# simp1.net
KiCad netlist of a schematic drawn in EAGLE
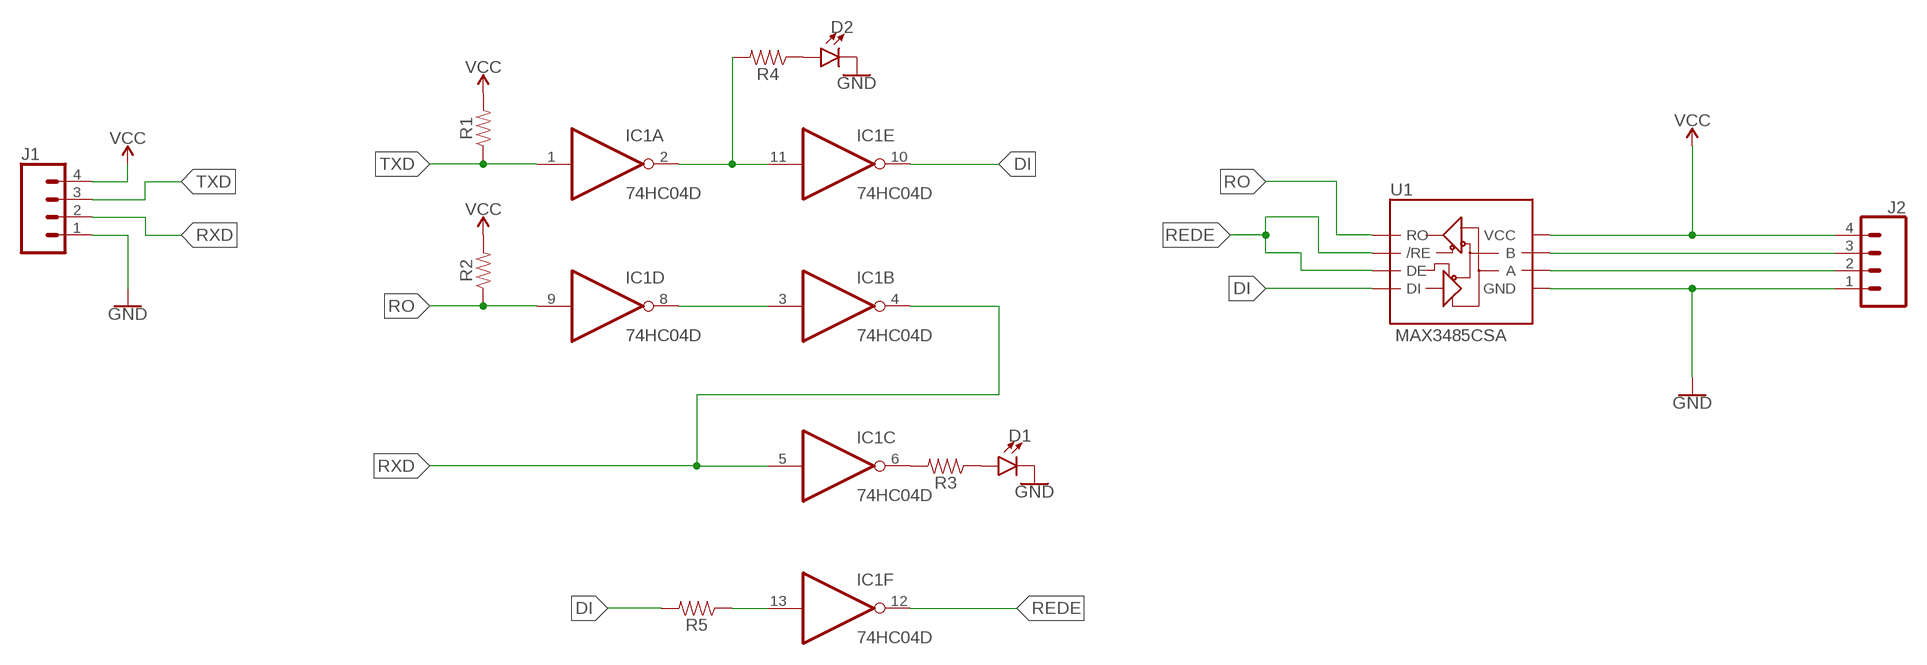
[diagram p0: schematic, sheet 1]

(export (version "E")
  (design (tool "Eeschema 10.0.6"))
  (components
    (comp (ref "D1")
      (value "LED0603")
      (footprint "eagle-import:LED-0603")
      (libsource (lib "eagle-import") (part "LED0603"))
    )
    (comp (ref "D2")
      (value "LED0603")
      (footprint "eagle-import:LED-0603")
      (libsource (lib "eagle-import") (part "LED0603"))
    )
    (comp (ref "IC1")
      (value "74HC04D")
      (footprint "eagle-import:SO14")
      (libsource (lib "eagle-import") (part "7404DHC"))
    )
    (comp (ref "J1")
      (value "CONN_04PTH")
      (footprint "eagle-import:1X04")
      (libsource (lib "eagle-import") (part "CONN_04PTH"))
    )
    (comp (ref "J2")
      (value "CONN_04PTH")
      (footprint "eagle-import:1X04")
      (libsource (lib "eagle-import") (part "CONN_04PTH"))
    )
    (comp (ref "R1")
      (value "RESISTOR0603")
      (footprint "eagle-import:0603")
      (libsource (lib "eagle-import") (part "RESISTOR0603"))
    )
    (comp (ref "R2")
      (value "RESISTOR0603")
      (footprint "eagle-import:0603")
      (libsource (lib "eagle-import") (part "RESISTOR0603"))
    )
    (comp (ref "R3")
      (value "RESISTOR0603")
      (footprint "eagle-import:0603")
      (libsource (lib "eagle-import") (part "RESISTOR0603"))
    )
    (comp (ref "R4")
      (value "RESISTOR0603")
      (footprint "eagle-import:0603")
      (libsource (lib "eagle-import") (part "RESISTOR0603"))
    )
    (comp (ref "R5")
      (value "RESISTOR0603")
      (footprint "eagle-import:0603")
      (libsource (lib "eagle-import") (part "RESISTOR0603"))
    )
    (comp (ref "U1")
      (value "MAX3485CSA")
      (footprint "eagle-import:SO08")
      (libsource (lib "eagle-import") (part "RS485SOIC"))
    )
  )
  (nets
    (net (code "1") (name "DI") (class "Default")
      (node (ref "IC1") (pin "10") (pinfunction "O_10") (pintype "output"))
      (node (ref "R5") (pin "2") (pinfunction "2_2") (pintype "passive"))
      (node (ref "U1") (pin "4") (pinfunction "DI_4") (pintype "bidirectional"))
    )
    (net (code "2") (name "GND") (class "Default")
      (node (ref "D1") (pin "C") (pinfunction "C_C") (pintype "passive"))
      (node (ref "D2") (pin "C") (pinfunction "C_C") (pintype "passive"))
      (node (ref "J1") (pin "1") (pinfunction "1_1") (pintype "passive"))
      (node (ref "J2") (pin "1") (pinfunction "1_1") (pintype "passive"))
      (node (ref "U1") (pin "5") (pinfunction "GND_5") (pintype "bidirectional"))
    )
    (net (code "3") (name "Net-(D1-PadA)") (class "Default")
      (node (ref "D1") (pin "A") (pinfunction "A_A") (pintype "passive"))
      (node (ref "R3") (pin "1") (pinfunction "1_1") (pintype "passive"))
    )
    (net (code "4") (name "Net-(D2-PadA)") (class "Default")
      (node (ref "D2") (pin "A") (pinfunction "A_A") (pintype "passive"))
      (node (ref "R4") (pin "1") (pinfunction "1_1") (pintype "passive"))
    )
    (net (code "5") (name "Net-(IC1A-O)") (class "Default")
      (node (ref "IC1") (pin "11") (pinfunction "I_11") (pintype "input"))
      (node (ref "IC1") (pin "2") (pinfunction "O_2") (pintype "output"))
      (node (ref "R4") (pin "2") (pinfunction "2_2") (pintype "passive"))
    )
    (net (code "6") (name "Net-(IC1B-I)") (class "Default")
      (node (ref "IC1") (pin "3") (pinfunction "I_3") (pintype "input"))
      (node (ref "IC1") (pin "8") (pinfunction "O_8") (pintype "output"))
    )
    (net (code "7") (name "Net-(IC1C-O)") (class "Default")
      (node (ref "IC1") (pin "6") (pinfunction "O_6") (pintype "output"))
      (node (ref "R3") (pin "2") (pinfunction "2_2") (pintype "passive"))
    )
    (net (code "8") (name "Net-(IC1F-I)") (class "Default")
      (node (ref "IC1") (pin "13") (pinfunction "I_13") (pintype "input"))
      (node (ref "R5") (pin "1") (pinfunction "1_1") (pintype "passive"))
    )
    (net (code "9") (name "Net-(U1-A)") (class "Default")
      (node (ref "J2") (pin "2") (pinfunction "2_2") (pintype "passive"))
      (node (ref "U1") (pin "6") (pinfunction "A_6") (pintype "bidirectional"))
    )
    (net (code "10") (name "Net-(U1-B)") (class "Default")
      (node (ref "J2") (pin "3") (pinfunction "3_3") (pintype "passive"))
      (node (ref "U1") (pin "7") (pinfunction "B_7") (pintype "bidirectional"))
    )
    (net (code "11") (name "REDE") (class "Default")
      (node (ref "IC1") (pin "12") (pinfunction "O_12") (pintype "output"))
      (node (ref "U1") (pin "2") (pinfunction "/RE_2") (pintype "bidirectional"))
      (node (ref "U1") (pin "3") (pinfunction "DE_3") (pintype "bidirectional"))
    )
    (net (code "12") (name "RO") (class "Default")
      (node (ref "IC1") (pin "9") (pinfunction "I_9") (pintype "input"))
      (node (ref "R2") (pin "1") (pinfunction "1_1") (pintype "passive"))
      (node (ref "U1") (pin "1") (pinfunction "RO_1") (pintype "bidirectional"))
    )
    (net (code "13") (name "RXD") (class "Default")
      (node (ref "IC1") (pin "4") (pinfunction "O_4") (pintype "output"))
      (node (ref "IC1") (pin "5") (pinfunction "I_5") (pintype "input"))
      (node (ref "J1") (pin "2") (pinfunction "2_2") (pintype "passive"))
    )
    (net (code "14") (name "TXD") (class "Default")
      (node (ref "IC1") (pin "1") (pinfunction "I_1") (pintype "input"))
      (node (ref "J1") (pin "3") (pinfunction "3_3") (pintype "passive"))
      (node (ref "R1") (pin "1") (pinfunction "1_1") (pintype "passive"))
    )
    (net (code "15") (name "VCC") (class "Default")
      (node (ref "J1") (pin "4") (pinfunction "4_4") (pintype "passive"))
      (node (ref "J2") (pin "4") (pinfunction "4_4") (pintype "passive"))
      (node (ref "R1") (pin "2") (pinfunction "2_2") (pintype "passive"))
      (node (ref "R2") (pin "2") (pinfunction "2_2") (pintype "passive"))
      (node (ref "U1") (pin "8") (pinfunction "VCC_8") (pintype "bidirectional"))
    )
  )
)
